# 3_amplifier.net
KiCad netlist of a schematic drawn in Altium Designer
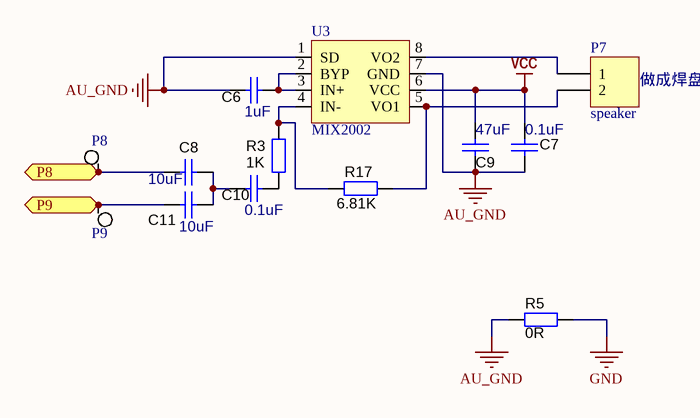
[diagram p0: 3 amplifier.SchDoc]

(export (version "E")
  (design (tool "Eeschema 10.0.6"))
  (components
    (comp (ref "C6")
      (value "1uF")
      (footprint "0402")
      (description "CAP, CERM, 0.01uF, 100V, +/-5%, X7R, 0603")
      (fields (field (name "PARTNUMBER") "06031C103JAT2A") (field (name "MANUFACTURER") "AVX"))
      (libsource (lib "03.常用器件") (part "CAP1_npol"))
    )
    (comp (ref "C7")
      (value "0.1uF")
      (footprint "0402")
      (description "CAP, CERM, 0.01uF, 100V, +/-5%, X7R, 0603")
      (fields (field (name "PARTNUMBER") "06031C103JAT2A") (field (name "MANUFACTURER") "AVX"))
      (libsource (lib "03.常用器件") (part "CAP1_npol"))
    )
    (comp (ref "C8")
      (value "10uF")
      (footprint "0603")
      (description "CAP, CERM, 0.01uF, 100V, +/-5%, X7R, 0603")
      (fields (field (name "PARTNUMBER") "06031C103JAT2A") (field (name "MANUFACTURER") "AVX"))
      (libsource (lib "03.常用器件") (part "CAP1_npol"))
    )
    (comp (ref "C9")
      (value "47uF")
      (footprint "0805")
      (description "CAP, CERM, 0.01uF, 100V, +/-5%, X7R, 0603")
      (fields (field (name "PARTNUMBER") "06031C103JAT2A") (field (name "MANUFACTURER") "AVX"))
      (libsource (lib "03.常用器件") (part "CAP1_npol"))
    )
    (comp (ref "C10")
      (value "0.1uF")
      (footprint "0402")
      (description "CAP, CERM, 0.01uF, 100V, +/-5%, X7R, 0603")
      (fields (field (name "PARTNUMBER") "06031C103JAT2A") (field (name "MANUFACTURER") "AVX"))
      (libsource (lib "03.常用器件") (part "CAP1_npol"))
    )
    (comp (ref "C11")
      (value "10uF")
      (footprint "0603")
      (description "CAP, CERM, 0.01uF, 100V, +/-5%, X7R, 0603")
      (fields (field (name "PARTNUMBER") "06031C103JAT2A") (field (name "MANUFACTURER") "AVX"))
      (libsource (lib "03.常用器件") (part "CAP1_npol"))
    )
    (comp (ref "P7")
      (value "speaker")
      (footprint "焊盘")
      (description "Header, 2-Pin")
      (fields (field (name "PUBLISHER") "Altium Limited"))
      (libsource (lib "Miscellaneous Connectors") (part "Header 2"))
    )
    (comp (ref "P8")
      (value "~")
      (footprint "测试点")
      (description "Test Point")
      (libsource (lib "my_Schlib") (part "TP"))
    )
    (comp (ref "P9")
      (value "~")
      (footprint "测试点")
      (description "Test Point")
      (libsource (lib "my_Schlib") (part "TP"))
    )
    (comp (ref "R3")
      (value "1K")
      (footprint "0402")
      (description "RES, 1.0k ohm, 5%, 0.1W, 0603")
      (fields
        (field (name "PARTNUMBER") "RC0603JR-071KL")
        (field (name "MANUFACTURER") "Yageo America")
        (field (name "PUBLISHER") "Texas Instruments")
      )
      (libsource (lib "") (part "RES1_2"))
    )
    (comp (ref "R5")
      (value "0R")
      (footprint "0402")
      (description "RES, 1.0k ohm, 5%, 0.1W, 0603")
      (fields
        (field (name "PARTNUMBER") "RC0603JR-071KL")
        (field (name "MANUFACTURER") "Yageo America")
        (field (name "PUBLISHER") "Texas Instruments")
      )
      (libsource (lib "03.常用器件") (part "RES1"))
    )
    (comp (ref "R17")
      (value "6.81K")
      (footprint "0402")
      (description "RES, 1.0k ohm, 5%, 0.1W, 0603")
      (fields
        (field (name "PARTNUMBER") "RC0603JR-071KL")
        (field (name "MANUFACTURER") "Yageo America")
        (field (name "PUBLISHER") "Texas Instruments")
      )
      (libsource (lib "") (part "RES1_1"))
    )
    (comp (ref "U3") (value "MIX2002") (footprint "SOP-8") (libsource (lib "Schlib1") (part "MIX2002")))
  )
  (nets
    (net (code "1") (name "/P8") (class "Default")
      (node (ref "C8") (pin "2") (pinfunction "2_2") (pintype "passive"))
      (node (ref "P8") (pin "1") (pinfunction "1_1") (pintype "passive"))
    )
    (net (code "2") (name "/P9") (class "Default")
      (node (ref "C11") (pin "2") (pinfunction "2_2") (pintype "passive"))
      (node (ref "P9") (pin "1") (pinfunction "1_1") (pintype "passive"))
    )
    (net (code "3") (name "AU_GND") (class "Default")
      (node (ref "C6") (pin "1") (pinfunction "1_1") (pintype "passive"))
      (node (ref "C7") (pin "2") (pinfunction "2_2") (pintype "passive"))
      (node (ref "C9") (pin "2") (pinfunction "2_2") (pintype "passive"))
      (node (ref "R5") (pin "2") (pinfunction "2_2") (pintype "passive"))
      (node (ref "U3") (pin "1") (pinfunction "SD_1") (pintype "passive"))
      (node (ref "U3") (pin "7") (pinfunction "GND_7") (pintype "passive"))
    )
    (net (code "4") (name "GND") (class "Default")
      (node (ref "R5") (pin "1") (pinfunction "1_1") (pintype "passive"))
    )
    (net (code "5") (name "Net-(C10-Pad1)") (class "Default")
      (node (ref "C10") (pin "1") (pinfunction "1_1") (pintype "passive"))
      (node (ref "C11") (pin "1") (pinfunction "1_1") (pintype "passive"))
      (node (ref "C8") (pin "1") (pinfunction "1_1") (pintype "passive"))
    )
    (net (code "6") (name "Net-(C10-Pad2)") (class "Default")
      (node (ref "C10") (pin "2") (pinfunction "2_2") (pintype "passive"))
      (node (ref "R3") (pin "1") (pinfunction "1_1") (pintype "passive"))
    )
    (net (code "7") (name "Net-(U3-BYP)") (class "Default")
      (node (ref "C6") (pin "2") (pinfunction "2_2") (pintype "passive"))
      (node (ref "U3") (pin "2") (pinfunction "BYP_2") (pintype "passive"))
      (node (ref "U3") (pin "3") (pinfunction "IN+_3") (pintype "passive"))
    )
    (net (code "8") (name "Net-(U3-IN-)") (class "Default")
      (node (ref "R17") (pin "1") (pinfunction "1_1") (pintype "passive"))
      (node (ref "R3") (pin "2") (pinfunction "2_2") (pintype "passive"))
      (node (ref "U3") (pin "4") (pinfunction "IN-_4") (pintype "passive"))
    )
    (net (code "9") (name "Net-(U3-VO1)") (class "Default")
      (node (ref "P7") (pin "2") (pinfunction "2_2") (pintype "passive"))
      (node (ref "R17") (pin "2") (pinfunction "2_2") (pintype "passive"))
      (node (ref "U3") (pin "5") (pinfunction "VO1_5") (pintype "passive"))
    )
    (net (code "10") (name "Net-(U3-VO2)") (class "Default")
      (node (ref "P7") (pin "1") (pinfunction "1_1") (pintype "passive"))
      (node (ref "U3") (pin "8") (pinfunction "VO2_8") (pintype "passive"))
    )
    (net (code "11") (name "VCC") (class "Default")
      (node (ref "C7") (pin "1") (pinfunction "1_1") (pintype "passive"))
      (node (ref "C9") (pin "1") (pinfunction "1_1") (pintype "passive"))
      (node (ref "U3") (pin "6") (pinfunction "VCC_6") (pintype "passive"))
    )
  )
)
